# slew_rate_control_w_gp.net
KiCad netlist of a schematic drawn in EAGLE
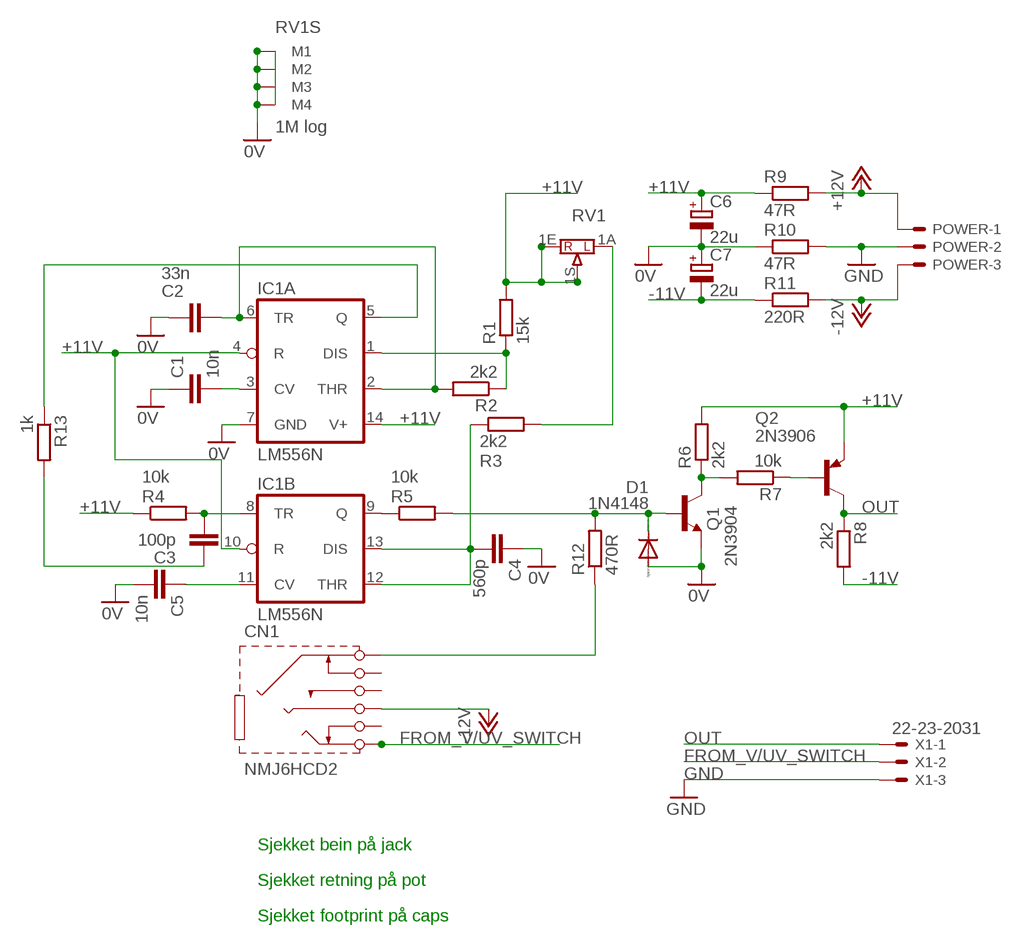
[diagram p0: schematic, sheet 1]

(export (version "E")
  (design (tool "Eeschema 10.0.6"))
  (components
    (comp (ref "C1")
      (value "10n")
      (footprint "eagle-import:C025-025X050")
      (libsource (lib "eagle-import") (part "resistor_C-EU025-025X050"))
    )
    (comp (ref "C2")
      (value "33n")
      (footprint "eagle-import:C075-032X103")
      (libsource (lib "eagle-import") (part "resistor_C-EU075-032X103"))
    )
    (comp (ref "C3")
      (value "100p")
      (footprint "eagle-import:C025-025X050")
      (libsource (lib "eagle-import") (part "resistor_C-EU025-025X050"))
    )
    (comp (ref "C4")
      (value "560p")
      (footprint "eagle-import:C025-025X050")
      (libsource (lib "eagle-import") (part "C-EU025-025X050"))
    )
    (comp (ref "C5")
      (value "10n")
      (footprint "eagle-import:C025-025X050")
      (libsource (lib "eagle-import") (part "resistor_C-EU025-025X050"))
    )
    (comp (ref "C6")
      (value "22u")
      (footprint "eagle-import:E2,5-5")
      (libsource (lib "eagle-import") (part "CPOL-EUE2.5-5"))
    )
    (comp (ref "C7")
      (value "22u")
      (footprint "eagle-import:E2,5-5")
      (libsource (lib "eagle-import") (part "CPOL-EUE2.5-5"))
    )
    (comp (ref "CN1")
      (value "NMJ6HCD2")
      (footprint "eagle-import:NMJ6HCD2")
      (libsource (lib "eagle-import") (part "NMJ6HCD2"))
    )
    (comp (ref "D1")
      (value "1N4148")
      (footprint "eagle-import:DO35-5J")
      (libsource (lib "eagle-import") (part "1N4148DOJ35-5"))
    )
    (comp (ref "IC1")
      (value "LM556N")
      (footprint "eagle-import:DIL14")
      (libsource (lib "eagle-import") (part "556NLM"))
    )
    (comp (ref "POWER")
      (value "KK-156-3")
      (footprint "eagle-import:KK-156-3")
      (libsource (lib "eagle-import") (part "KK-156-3"))
    )
    (comp (ref "Q1")
      (value "2N3904")
      (footprint "eagle-import:TO92")
      (libsource (lib "eagle-import") (part "2N3904"))
    )
    (comp (ref "Q2")
      (value "2N3906")
      (footprint "eagle-import:TO92")
      (libsource (lib "eagle-import") (part "2N3906"))
    )
    (comp (ref "R1")
      (value "15k")
      (footprint "eagle-import:0207_7")
      (libsource (lib "eagle-import") (part "R-EU_0207/7"))
    )
    (comp (ref "R2")
      (value "2k2")
      (footprint "eagle-import:0207_7")
      (libsource (lib "eagle-import") (part "R-EU_0207/7"))
    )
    (comp (ref "R3")
      (value "2k2")
      (footprint "eagle-import:0207_7")
      (libsource (lib "eagle-import") (part "R-EU_0207/7"))
    )
    (comp (ref "R4")
      (value "10k")
      (footprint "eagle-import:0207_7")
      (libsource (lib "eagle-import") (part "R-EU_0207/7"))
    )
    (comp (ref "R5")
      (value "10k")
      (footprint "eagle-import:0207_7")
      (libsource (lib "eagle-import") (part "R-EU_0207/7"))
    )
    (comp (ref "R6")
      (value "2k2")
      (footprint "eagle-import:0207_7")
      (libsource (lib "eagle-import") (part "R-EU_0207/7"))
    )
    (comp (ref "R7")
      (value "10k")
      (footprint "eagle-import:0207_7")
      (libsource (lib "eagle-import") (part "R-EU_0207/7"))
    )
    (comp (ref "R8")
      (value "2k2")
      (footprint "eagle-import:0207_7")
      (libsource (lib "eagle-import") (part "R-EU_0207/7"))
    )
    (comp (ref "R9")
      (value "47R")
      (footprint "eagle-import:0207_7")
      (libsource (lib "eagle-import") (part "R-EU_0207/7"))
    )
    (comp (ref "R10")
      (value "47R")
      (footprint "eagle-import:0207_7")
      (libsource (lib "eagle-import") (part "R-EU_0207/7"))
    )
    (comp (ref "R11")
      (value "220R")
      (footprint "eagle-import:0207_7")
      (libsource (lib "eagle-import") (part "R-EU_0207/7"))
    )
    (comp (ref "R12")
      (value "470R")
      (footprint "eagle-import:0207_7")
      (libsource (lib "eagle-import") (part "R-EU_0207/7"))
    )
    (comp (ref "R13")
      (value "1k")
      (footprint "eagle-import:0207_7")
      (libsource (lib "eagle-import") (part "R-EU_0207/7"))
    )
    (comp (ref "RV1")
      (value "1M log")
      (footprint "eagle-import:POT16_W_BRACKET")
      (libsource (lib "eagle-import") (part "POT16_W_BRACKET{dblquote}{dblquote}"))
    )
    (comp (ref "X1")
      (value "22-23-2031")
      (footprint "eagle-import:22-23-2031")
      (fields (field (name "MF") "MOLEX"))
      (libsource (lib "eagle-import") (part "22-23-2031"))
    )
  )
  (nets
    (net (code "1") (name "+12V") (class "Default")
      (node (ref "POWER") (pin "1") (pinfunction "S_1") (pintype "passive"))
      (node (ref "R9") (pin "2") (pinfunction "2_2") (pintype "passive"))
    )
    (net (code "2") (name "-12V") (class "Default")
      (node (ref "CN1") (pin "R") (pinfunction "RING_R") (pintype "passive"))
      (node (ref "POWER") (pin "3") (pinfunction "S_3") (pintype "passive"))
      (node (ref "R11") (pin "2") (pinfunction "2_2") (pintype "passive"))
    )
    (net (code "3") (name "/+11V") (class "Default")
      (node (ref "C6") (pin "+") (pinfunction "+_+") (pintype "passive"))
      (node (ref "IC1") (pin "10") (pinfunction "R_10") (pintype "input"))
      (node (ref "IC1") (pin "14") (pinfunction "V+_14") (pintype "power_in"))
      (node (ref "IC1") (pin "4") (pinfunction "R_4") (pintype "input"))
      (node (ref "Q2") (pin "3") (pinfunction "E_3") (pintype "passive"))
      (node (ref "R1") (pin "2") (pinfunction "2_2") (pintype "passive"))
      (node (ref "R4") (pin "1") (pinfunction "1_1") (pintype "passive"))
      (node (ref "R6") (pin "2") (pinfunction "2_2") (pintype "passive"))
      (node (ref "R9") (pin "1") (pinfunction "1_1") (pintype "passive"))
      (node (ref "RV1") (pin "1E") (pinfunction "1E_1E") (pintype "passive"))
      (node (ref "RV1") (pin "1S") (pinfunction "1S_1S") (pintype "passive"))
    )
    (net (code "4") (name "/-11V") (class "Default")
      (node (ref "C7") (pin "-") (pinfunction "-_-") (pintype "passive"))
      (node (ref "R11") (pin "1") (pinfunction "1_1") (pintype "passive"))
      (node (ref "R8") (pin "2") (pinfunction "2_2") (pintype "passive"))
    )
    (net (code "5") (name "/FROM_V{slash}UV_SWITCH") (class "Default")
      (node (ref "CN1") (pin "T") (pinfunction "TIP_T") (pintype "passive"))
      (node (ref "X1") (pin "2") (pinfunction "S_2") (pintype "passive"))
    )
    (net (code "6") (name "/OUT") (class "Default")
      (node (ref "Q2") (pin "1") (pinfunction "C_1") (pintype "passive"))
      (node (ref "R8") (pin "1") (pinfunction "1_1") (pintype "passive"))
      (node (ref "X1") (pin "1") (pinfunction "S_1") (pintype "passive"))
    )
    (net (code "7") (name "0V") (class "Default")
      (node (ref "C1") (pin "1") (pinfunction "1_1") (pintype "passive"))
      (node (ref "C2") (pin "2") (pinfunction "2_2") (pintype "passive"))
      (node (ref "C4") (pin "1") (pinfunction "1_1") (pintype "passive"))
      (node (ref "C5") (pin "2") (pinfunction "2_2") (pintype "passive"))
      (node (ref "C6") (pin "-") (pinfunction "-_-") (pintype "passive"))
      (node (ref "C7") (pin "+") (pinfunction "+_+") (pintype "passive"))
      (node (ref "D1") (pin "A") (pinfunction "A_A") (pintype "passive"))
      (node (ref "IC1") (pin "7") (pinfunction "GND_7") (pintype "power_in"))
      (node (ref "Q1") (pin "3") (pinfunction "E_3") (pintype "passive"))
      (node (ref "R10") (pin "1") (pinfunction "1_1") (pintype "passive"))
      (node (ref "RV1") (pin "M1") (pinfunction "M1_M1") (pintype "passive"))
      (node (ref "RV1") (pin "M2") (pinfunction "M2_M2") (pintype "passive"))
      (node (ref "RV1") (pin "M3") (pinfunction "M3_M3") (pintype "passive"))
      (node (ref "RV1") (pin "M4") (pinfunction "M4_M4") (pintype "passive"))
    )
    (net (code "8") (name "GND") (class "Default")
      (node (ref "POWER") (pin "2") (pinfunction "S_2") (pintype "passive"))
      (node (ref "R10") (pin "2") (pinfunction "2_2") (pintype "passive"))
      (node (ref "X1") (pin "3") (pinfunction "S_3") (pintype "passive"))
    )
    (net (code "9") (name "Net-(C3-Pad1)") (class "Default")
      (node (ref "C3") (pin "1") (pinfunction "1_1") (pintype "passive"))
      (node (ref "R13") (pin "2") (pinfunction "2_2") (pintype "passive"))
    )
    (net (code "10") (name "Net-(CN1-SLEEVE)") (class "Default")
      (node (ref "CN1") (pin "S") (pinfunction "SLEEVE_S") (pintype "passive"))
      (node (ref "R12") (pin "1") (pinfunction "1_1") (pintype "passive"))
    )
    (net (code "11") (name "Net-(IC1A-CV)") (class "Default")
      (node (ref "C1") (pin "2") (pinfunction "2_2") (pintype "passive"))
      (node (ref "IC1") (pin "3") (pinfunction "CV_3") (pintype "input"))
    )
    (net (code "12") (name "Net-(IC1A-DIS)") (class "Default")
      (node (ref "IC1") (pin "1") (pinfunction "DIS_1") (pintype "input"))
      (node (ref "R1") (pin "1") (pinfunction "1_1") (pintype "passive"))
      (node (ref "R2") (pin "1") (pinfunction "1_1") (pintype "passive"))
    )
    (net (code "13") (name "Net-(IC1A-Q)") (class "Default")
      (node (ref "IC1") (pin "5") (pinfunction "Q_5") (pintype "output"))
      (node (ref "R13") (pin "1") (pinfunction "1_1") (pintype "passive"))
    )
    (net (code "14") (name "Net-(IC1A-THR)") (class "Default")
      (node (ref "C2") (pin "1") (pinfunction "1_1") (pintype "passive"))
      (node (ref "IC1") (pin "2") (pinfunction "THR_2") (pintype "input"))
      (node (ref "IC1") (pin "6") (pinfunction "TR_6") (pintype "input"))
      (node (ref "R2") (pin "2") (pinfunction "2_2") (pintype "passive"))
    )
    (net (code "15") (name "Net-(IC1B-CV)") (class "Default")
      (node (ref "C5") (pin "1") (pinfunction "1_1") (pintype "passive"))
      (node (ref "IC1") (pin "11") (pinfunction "CV_11") (pintype "input"))
    )
    (net (code "16") (name "Net-(IC1B-DIS)") (class "Default")
      (node (ref "C4") (pin "2") (pinfunction "2_2") (pintype "passive"))
      (node (ref "IC1") (pin "12") (pinfunction "THR_12") (pintype "input"))
      (node (ref "IC1") (pin "13") (pinfunction "DIS_13") (pintype "input"))
      (node (ref "R3") (pin "1") (pinfunction "1_1") (pintype "passive"))
    )
    (net (code "17") (name "Net-(IC1B-Q)") (class "Default")
      (node (ref "IC1") (pin "9") (pinfunction "Q_9") (pintype "output"))
      (node (ref "R5") (pin "1") (pinfunction "1_1") (pintype "passive"))
    )
    (net (code "18") (name "Net-(IC1B-TR)") (class "Default")
      (node (ref "C3") (pin "2") (pinfunction "2_2") (pintype "passive"))
      (node (ref "IC1") (pin "8") (pinfunction "TR_8") (pintype "input"))
      (node (ref "R4") (pin "2") (pinfunction "2_2") (pintype "passive"))
    )
    (net (code "19") (name "Net-(Q1-B)") (class "Default")
      (node (ref "D1") (pin "C") (pinfunction "C_C") (pintype "passive"))
      (node (ref "Q1") (pin "2") (pinfunction "B_2") (pintype "passive"))
      (node (ref "R12") (pin "2") (pinfunction "2_2") (pintype "passive"))
      (node (ref "R5") (pin "2") (pinfunction "2_2") (pintype "passive"))
    )
    (net (code "20") (name "Net-(Q1-C)") (class "Default")
      (node (ref "Q1") (pin "1") (pinfunction "C_1") (pintype "passive"))
      (node (ref "R6") (pin "1") (pinfunction "1_1") (pintype "passive"))
      (node (ref "R7") (pin "2") (pinfunction "2_2") (pintype "passive"))
    )
    (net (code "21") (name "Net-(Q2-B)") (class "Default")
      (node (ref "Q2") (pin "2") (pinfunction "B_2") (pintype "passive"))
      (node (ref "R7") (pin "1") (pinfunction "1_1") (pintype "passive"))
    )
    (net (code "22") (name "Net-(R3-Pad2)") (class "Default")
      (node (ref "R3") (pin "2") (pinfunction "2_2") (pintype "passive"))
      (node (ref "RV1") (pin "1A") (pinfunction "1A_1A") (pintype "passive"))
    )
    (net (code "23") (name "unconnected-(CN1-RING-S-PadRN)") (class "Default")
      (node (ref "CN1") (pin "RN") (pinfunction "RING-S_RN") (pintype "passive"))
    )
    (net (code "24") (name "unconnected-(CN1-SLEEVE-S-PadSN)") (class "Default")
      (node (ref "CN1") (pin "SN") (pinfunction "SLEEVE-S_SN") (pintype "passive"))
    )
    (net (code "25") (name "unconnected-(CN1-TIP-S-PadTN)") (class "Default")
      (node (ref "CN1") (pin "TN") (pinfunction "TIP-S_TN") (pintype "passive"))
    )
  )
)
